# Solar_Simulator.net
KiCad netlist of a schematic drawn in EAGLE
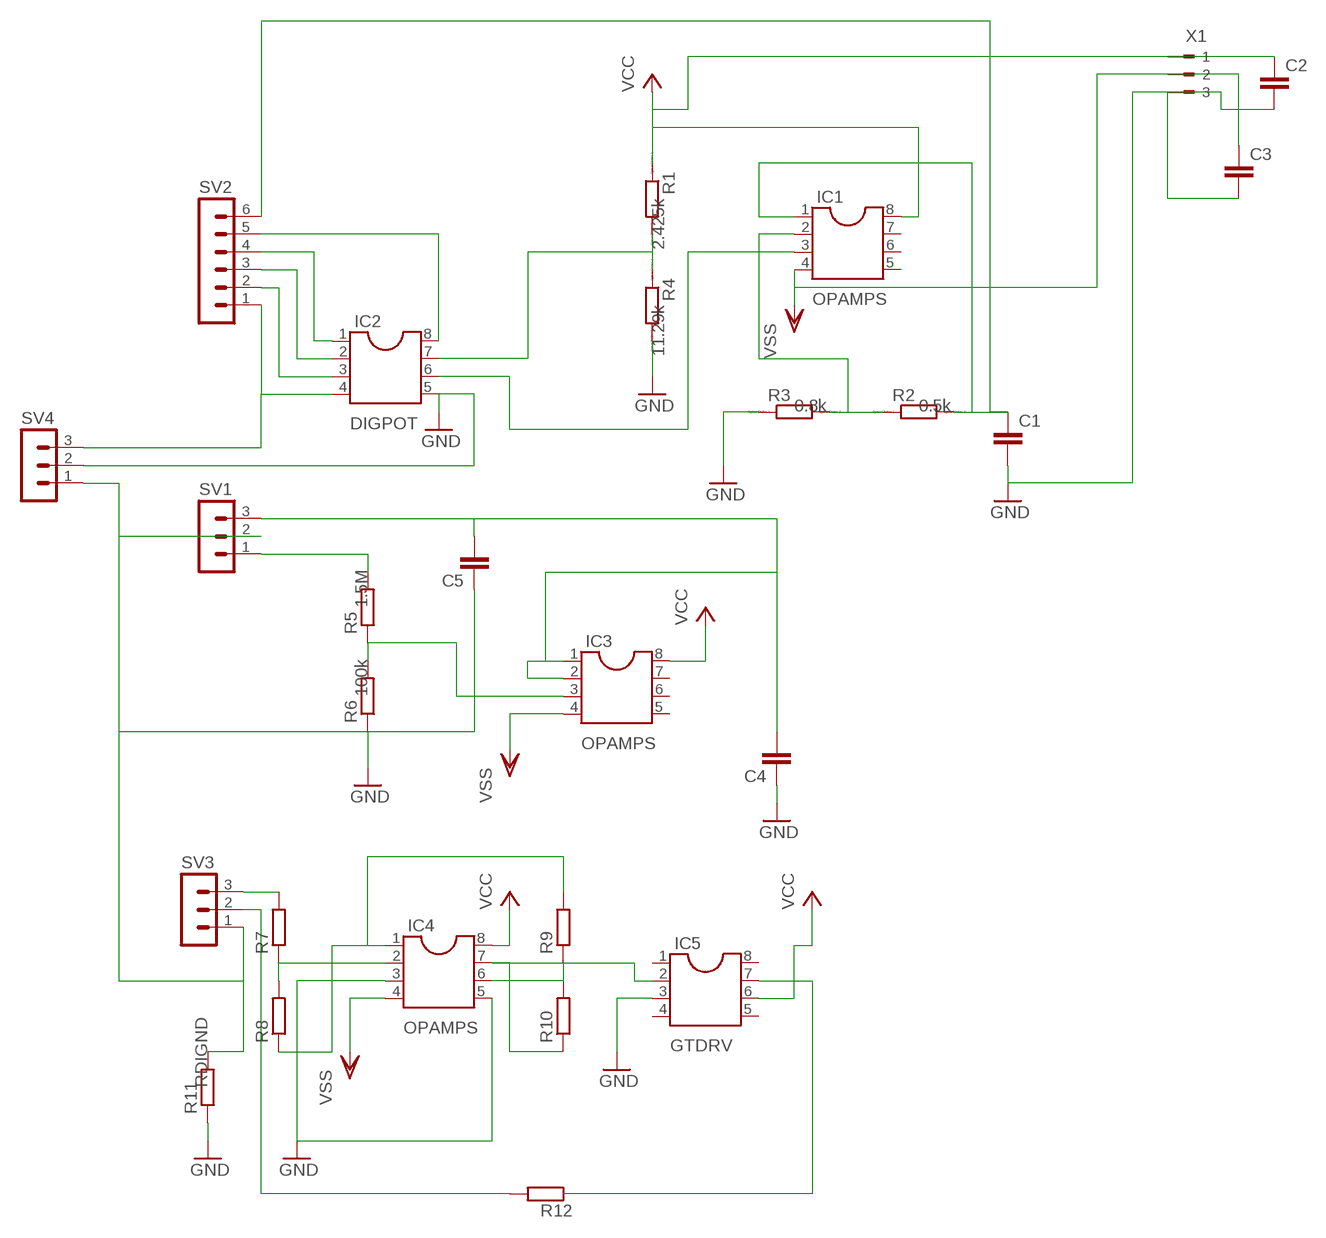
[diagram p0: schematic, sheet 1]

(export (version "E")
  (design (tool "Eeschema 10.0.6"))
  (components
    (comp (ref "C1")
      (value "C5/2.5")
      (footprint "eagle-import:C5B2.5")
      (libsource (lib "eagle-import") (part "C5/2.5"))
    )
    (comp (ref "C2")
      (value "C5/2.5")
      (footprint "eagle-import:C5B2.5")
      (libsource (lib "eagle-import") (part "C5/2.5"))
    )
    (comp (ref "C3")
      (value "C5/2.5")
      (footprint "eagle-import:C5B2.5")
      (libsource (lib "eagle-import") (part "C5/2.5"))
    )
    (comp (ref "C4")
      (value "C5/2.5")
      (footprint "eagle-import:C5B2.5")
      (libsource (lib "eagle-import") (part "C5/2.5"))
    )
    (comp (ref "C5")
      (value "C5/2.5")
      (footprint "eagle-import:C5B2.5")
      (libsource (lib "eagle-import") (part "C5/2.5"))
    )
    (comp (ref "IC1")
      (value "DIL8S")
      (footprint "eagle-import:SOCKET-08")
      (libsource (lib "eagle-import") (part "DIL8S"))
    )
    (comp (ref "IC2")
      (value "DIL8S")
      (footprint "eagle-import:SOCKET-08")
      (libsource (lib "eagle-import") (part "DIL8S"))
    )
    (comp (ref "IC3")
      (value "DIL8S")
      (footprint "eagle-import:SOCKET-08")
      (libsource (lib "eagle-import") (part "DIL8S"))
    )
    (comp (ref "IC4")
      (value "DIL8S")
      (footprint "eagle-import:SOCKET-08")
      (libsource (lib "eagle-import") (part "DIL8S"))
    )
    (comp (ref "IC5")
      (value "DIL8S")
      (footprint "eagle-import:SOCKET-08")
      (libsource (lib "eagle-import") (part "DIL8S"))
    )
    (comp (ref "R1")
      (value "R0207/10")
      (footprint "eagle-import:0207_10")
      (fields (field (name "SPICEMODEL") "NONE") (field (name "SPICEMODEL_1") "2.425k"))
      (libsource (lib "eagle-import") (part "R0207/10"))
    )
    (comp (ref "R2")
      (value "R0207/10")
      (footprint "eagle-import:0207_10")
      (fields (field (name "SPICEMODEL") "NONE") (field (name "SPICEMODEL_1") "0.5k"))
      (libsource (lib "eagle-import") (part "R0207/10"))
    )
    (comp (ref "R3")
      (value "R0207/10")
      (footprint "eagle-import:0207_10")
      (fields (field (name "SPICEMODEL") "NONE") (field (name "SPICEMODEL_1") "0.8k"))
      (libsource (lib "eagle-import") (part "R0207/10"))
    )
    (comp (ref "R4")
      (value "R0207/10")
      (footprint "eagle-import:0207_10")
      (fields (field (name "SPICEMODEL") "NONE") (field (name "SPICEMODEL_1") "11.29k"))
      (libsource (lib "eagle-import") (part "R0207/10"))
    )
    (comp (ref "R5")
      (value "R-EU_0207/10")
      (footprint "eagle-import:0207_10")
      (fields (field (name "RR") "1.5M"))
      (libsource (lib "eagle-import") (part "R-EU_0207/10"))
    )
    (comp (ref "R6")
      (value "R-EU_0207/10")
      (footprint "eagle-import:0207_10")
      (fields (field (name "RR2") "100k"))
      (libsource (lib "eagle-import") (part "R-EU_0207/10"))
    )
    (comp (ref "R7")
      (value "R-EU_0207/10")
      (footprint "eagle-import:0207_10")
      (libsource (lib "eagle-import") (part "R-EU_0207/10"))
    )
    (comp (ref "R8")
      (value "R-EU_0207/10")
      (footprint "eagle-import:0207_10")
      (libsource (lib "eagle-import") (part "R-EU_0207/10"))
    )
    (comp (ref "R9")
      (value "R-EU_0207/10")
      (footprint "eagle-import:0207_10")
      (libsource (lib "eagle-import") (part "R-EU_0207/10"))
    )
    (comp (ref "R10")
      (value "R-EU_0207/10")
      (footprint "eagle-import:0207_10")
      (libsource (lib "eagle-import") (part "R-EU_0207/10"))
    )
    (comp (ref "R11")
      (value "R-EU_0207/10")
      (footprint "eagle-import:0207_10")
      (libsource (lib "eagle-import") (part "R-EU_0207/10"))
    )
    (comp (ref "R12")
      (value "R-EU_0207/10")
      (footprint "eagle-import:0207_10")
      (libsource (lib "eagle-import") (part "R-EU_0207/10"))
    )
    (comp (ref "SV1")
      (value "MA03-1")
      (footprint "eagle-import:MA03-1")
      (libsource (lib "eagle-import") (part "MA03-1"))
    )
    (comp (ref "SV2")
      (value "MA06-1")
      (footprint "eagle-import:MA06-1")
      (libsource (lib "eagle-import") (part "MA06-1"))
    )
    (comp (ref "SV3")
      (value "MA03-1")
      (footprint "eagle-import:MA03-1")
      (libsource (lib "eagle-import") (part "MA03-1"))
    )
    (comp (ref "SV4")
      (value "MA03-1")
      (footprint "eagle-import:MA03-1")
      (libsource (lib "eagle-import") (part "MA03-1"))
    )
    (comp (ref "X1")
      (value "90-3")
      (footprint "eagle-import:90-3")
      (libsource (lib "eagle-import") (part "90-3"))
    )
  )
  (nets
    (net (code "1") (name "GND") (class "Default")
      (node (ref "C1") (pin "2") (pinfunction "2_2") (pintype "passive"))
      (node (ref "C2") (pin "2") (pinfunction "2_2") (pintype "passive"))
      (node (ref "C3") (pin "2") (pinfunction "2_2") (pintype "passive"))
      (node (ref "C4") (pin "1") (pinfunction "1_1") (pintype "passive"))
      (node (ref "IC2") (pin "5") (pinfunction "5_5") (pintype "passive"))
      (node (ref "IC4") (pin "3") (pinfunction "3_3") (pintype "passive"))
      (node (ref "IC4") (pin "5") (pinfunction "5_5") (pintype "passive"))
      (node (ref "IC5") (pin "3") (pinfunction "3_3") (pintype "passive"))
      (node (ref "R11") (pin "1") (pinfunction "1_1") (pintype "passive"))
      (node (ref "R3") (pin "1") (pinfunction "1_1") (pintype "passive"))
      (node (ref "R4") (pin "2") (pinfunction "2_2") (pintype "passive"))
      (node (ref "R6") (pin "1") (pinfunction "1_1") (pintype "passive"))
      (node (ref "SV4") (pin "2") (pinfunction "2_2") (pintype "passive"))
      (node (ref "X1") (pin "3") (pinfunction "3_3") (pintype "passive"))
    )
    (net (code "2") (name "Net-(C1-Pad1)") (class "Default")
      (node (ref "C1") (pin "1") (pinfunction "1_1") (pintype "passive"))
      (node (ref "IC1") (pin "1") (pinfunction "1_1") (pintype "passive"))
      (node (ref "R2") (pin "2") (pinfunction "2_2") (pintype "passive"))
      (node (ref "SV2") (pin "6") (pinfunction "6_6") (pintype "passive"))
    )
    (net (code "3") (name "Net-(C4-Pad2)") (class "Default")
      (node (ref "C4") (pin "2") (pinfunction "2_2") (pintype "passive"))
      (node (ref "C5") (pin "2") (pinfunction "2_2") (pintype "passive"))
      (node (ref "IC3") (pin "1") (pinfunction "1_1") (pintype "passive"))
      (node (ref "IC3") (pin "2") (pinfunction "2_2") (pintype "passive"))
      (node (ref "SV1") (pin "3") (pinfunction "3_3") (pintype "passive"))
    )
    (net (code "4") (name "Net-(C5-Pad1)") (class "Default")
      (node (ref "C5") (pin "1") (pinfunction "1_1") (pintype "passive"))
      (node (ref "R11") (pin "2") (pinfunction "2_2") (pintype "passive"))
      (node (ref "SV1") (pin "2") (pinfunction "2_2") (pintype "passive"))
      (node (ref "SV3") (pin "1") (pinfunction "1_1") (pintype "passive"))
      (node (ref "SV4") (pin "1") (pinfunction "1_1") (pintype "passive"))
    )
    (net (code "5") (name "Net-(IC1-Pad2)") (class "Default")
      (node (ref "IC1") (pin "2") (pinfunction "2_2") (pintype "passive"))
      (node (ref "R2") (pin "1") (pinfunction "1_1") (pintype "passive"))
      (node (ref "R3") (pin "2") (pinfunction "2_2") (pintype "passive"))
    )
    (net (code "6") (name "Net-(IC1-Pad3)") (class "Default")
      (node (ref "IC1") (pin "3") (pinfunction "3_3") (pintype "passive"))
      (node (ref "IC2") (pin "6") (pinfunction "6_6") (pintype "passive"))
    )
    (net (code "7") (name "Net-(IC2-Pad1)") (class "Default")
      (node (ref "IC2") (pin "1") (pinfunction "1_1") (pintype "passive"))
      (node (ref "SV2") (pin "4") (pinfunction "4_4") (pintype "passive"))
    )
    (net (code "8") (name "Net-(IC2-Pad2)") (class "Default")
      (node (ref "IC2") (pin "2") (pinfunction "2_2") (pintype "passive"))
      (node (ref "SV2") (pin "3") (pinfunction "3_3") (pintype "passive"))
    )
    (net (code "9") (name "Net-(IC2-Pad3)") (class "Default")
      (node (ref "IC2") (pin "3") (pinfunction "3_3") (pintype "passive"))
      (node (ref "SV2") (pin "2") (pinfunction "2_2") (pintype "passive"))
    )
    (net (code "10") (name "Net-(IC2-Pad4)") (class "Default")
      (node (ref "IC2") (pin "4") (pinfunction "4_4") (pintype "passive"))
      (node (ref "SV2") (pin "1") (pinfunction "1_1") (pintype "passive"))
      (node (ref "SV4") (pin "3") (pinfunction "3_3") (pintype "passive"))
    )
    (net (code "11") (name "Net-(IC2-Pad7)") (class "Default")
      (node (ref "IC2") (pin "7") (pinfunction "7_7") (pintype "passive"))
      (node (ref "R1") (pin "2") (pinfunction "2_2") (pintype "passive"))
      (node (ref "R4") (pin "1") (pinfunction "1_1") (pintype "passive"))
    )
    (net (code "12") (name "Net-(IC2-Pad8)") (class "Default")
      (node (ref "IC2") (pin "8") (pinfunction "8_8") (pintype "passive"))
      (node (ref "SV2") (pin "5") (pinfunction "5_5") (pintype "passive"))
    )
    (net (code "13") (name "Net-(IC3-Pad3)") (class "Default")
      (node (ref "IC3") (pin "3") (pinfunction "3_3") (pintype "passive"))
      (node (ref "R5") (pin "1") (pinfunction "1_1") (pintype "passive"))
      (node (ref "R6") (pin "2") (pinfunction "2_2") (pintype "passive"))
    )
    (net (code "14") (name "Net-(IC4-Pad1)") (class "Default")
      (node (ref "IC4") (pin "1") (pinfunction "1_1") (pintype "passive"))
      (node (ref "R8") (pin "1") (pinfunction "1_1") (pintype "passive"))
      (node (ref "R9") (pin "2") (pinfunction "2_2") (pintype "passive"))
    )
    (net (code "15") (name "Net-(IC4-Pad2)") (class "Default")
      (node (ref "IC4") (pin "2") (pinfunction "2_2") (pintype "passive"))
      (node (ref "R7") (pin "1") (pinfunction "1_1") (pintype "passive"))
      (node (ref "R8") (pin "2") (pinfunction "2_2") (pintype "passive"))
    )
    (net (code "16") (name "Net-(IC4-Pad6)") (class "Default")
      (node (ref "IC4") (pin "6") (pinfunction "6_6") (pintype "passive"))
      (node (ref "R10") (pin "2") (pinfunction "2_2") (pintype "passive"))
      (node (ref "R9") (pin "1") (pinfunction "1_1") (pintype "passive"))
    )
    (net (code "17") (name "Net-(IC4-Pad7)") (class "Default")
      (node (ref "IC4") (pin "7") (pinfunction "7_7") (pintype "passive"))
      (node (ref "IC5") (pin "2") (pinfunction "2_2") (pintype "passive"))
      (node (ref "R10") (pin "1") (pinfunction "1_1") (pintype "passive"))
    )
    (net (code "18") (name "Net-(R5-Pad2)") (class "Default")
      (node (ref "R5") (pin "2") (pinfunction "2_2") (pintype "passive"))
      (node (ref "SV1") (pin "1") (pinfunction "1_1") (pintype "passive"))
    )
    (net (code "19") (name "Net-(R7-Pad2)") (class "Default")
      (node (ref "R7") (pin "2") (pinfunction "2_2") (pintype "passive"))
      (node (ref "SV3") (pin "3") (pinfunction "3_3") (pintype "passive"))
    )
    (net (code "20") (name "Net-(R12-Pad2)") (class "Default")
      (node (ref "R12") (pin "2") (pinfunction "2_2") (pintype "passive"))
      (node (ref "SV3") (pin "2") (pinfunction "2_2") (pintype "passive"))
    )
    (net (code "21") (name "VCC") (class "Default")
      (node (ref "C2") (pin "1") (pinfunction "1_1") (pintype "passive"))
      (node (ref "IC1") (pin "8") (pinfunction "8_8") (pintype "passive"))
      (node (ref "IC3") (pin "8") (pinfunction "8_8") (pintype "passive"))
      (node (ref "IC4") (pin "8") (pinfunction "8_8") (pintype "passive"))
      (node (ref "IC5") (pin "6") (pinfunction "6_6") (pintype "passive"))
      (node (ref "R1") (pin "1") (pinfunction "1_1") (pintype "passive"))
      (node (ref "X1") (pin "1") (pinfunction "1_1") (pintype "passive"))
    )
    (net (code "22") (name "VSS") (class "Default")
      (node (ref "C3") (pin "1") (pinfunction "1_1") (pintype "passive"))
      (node (ref "IC1") (pin "4") (pinfunction "4_4") (pintype "passive"))
      (node (ref "IC3") (pin "4") (pinfunction "4_4") (pintype "passive"))
      (node (ref "IC4") (pin "4") (pinfunction "4_4") (pintype "passive"))
      (node (ref "X1") (pin "2") (pinfunction "2_2") (pintype "passive"))
    )
    (net (code "23") (name "unconnected-(IC1-Pad5)") (class "Default")
      (node (ref "IC1") (pin "5") (pinfunction "5_5") (pintype "passive"))
    )
    (net (code "24") (name "unconnected-(IC1-Pad6)") (class "Default")
      (node (ref "IC1") (pin "6") (pinfunction "6_6") (pintype "passive"))
    )
    (net (code "25") (name "unconnected-(IC1-Pad7)") (class "Default")
      (node (ref "IC1") (pin "7") (pinfunction "7_7") (pintype "passive"))
    )
    (net (code "26") (name "unconnected-(IC3-Pad5)") (class "Default")
      (node (ref "IC3") (pin "5") (pinfunction "5_5") (pintype "passive"))
    )
    (net (code "27") (name "unconnected-(IC3-Pad6)") (class "Default")
      (node (ref "IC3") (pin "6") (pinfunction "6_6") (pintype "passive"))
    )
    (net (code "28") (name "unconnected-(IC3-Pad7)") (class "Default")
      (node (ref "IC3") (pin "7") (pinfunction "7_7") (pintype "passive"))
    )
    (net (code "29") (name "unconnected-(IC5-Pad1)") (class "Default")
      (node (ref "IC5") (pin "1") (pinfunction "1_1") (pintype "passive"))
    )
    (net (code "30") (name "unconnected-(IC5-Pad4)") (class "Default")
      (node (ref "IC5") (pin "4") (pinfunction "4_4") (pintype "passive"))
    )
    (net (code "31") (name "unconnected-(IC5-Pad5)") (class "Default")
      (node (ref "IC5") (pin "5") (pinfunction "5_5") (pintype "passive"))
    )
    (net (code "32") (name "unconnected-(IC5-Pad7)") (class "Default")
      (node (ref "IC5") (pin "7") (pinfunction "7_7") (pintype "passive"))
    )
    (net (code "33") (name "unconnected-(IC5-Pad8)") (class "Default")
      (node (ref "IC5") (pin "8") (pinfunction "8_8") (pintype "passive"))
    )
    (net (code "34") (name "unconnected-(R12-Pad1)") (class "Default")
      (node (ref "R12") (pin "1") (pinfunction "1_1") (pintype "passive"))
    )
  )
)
